# cdf-teensy-interrupter-v2.net
KiCad netlist of a schematic drawn in EAGLE
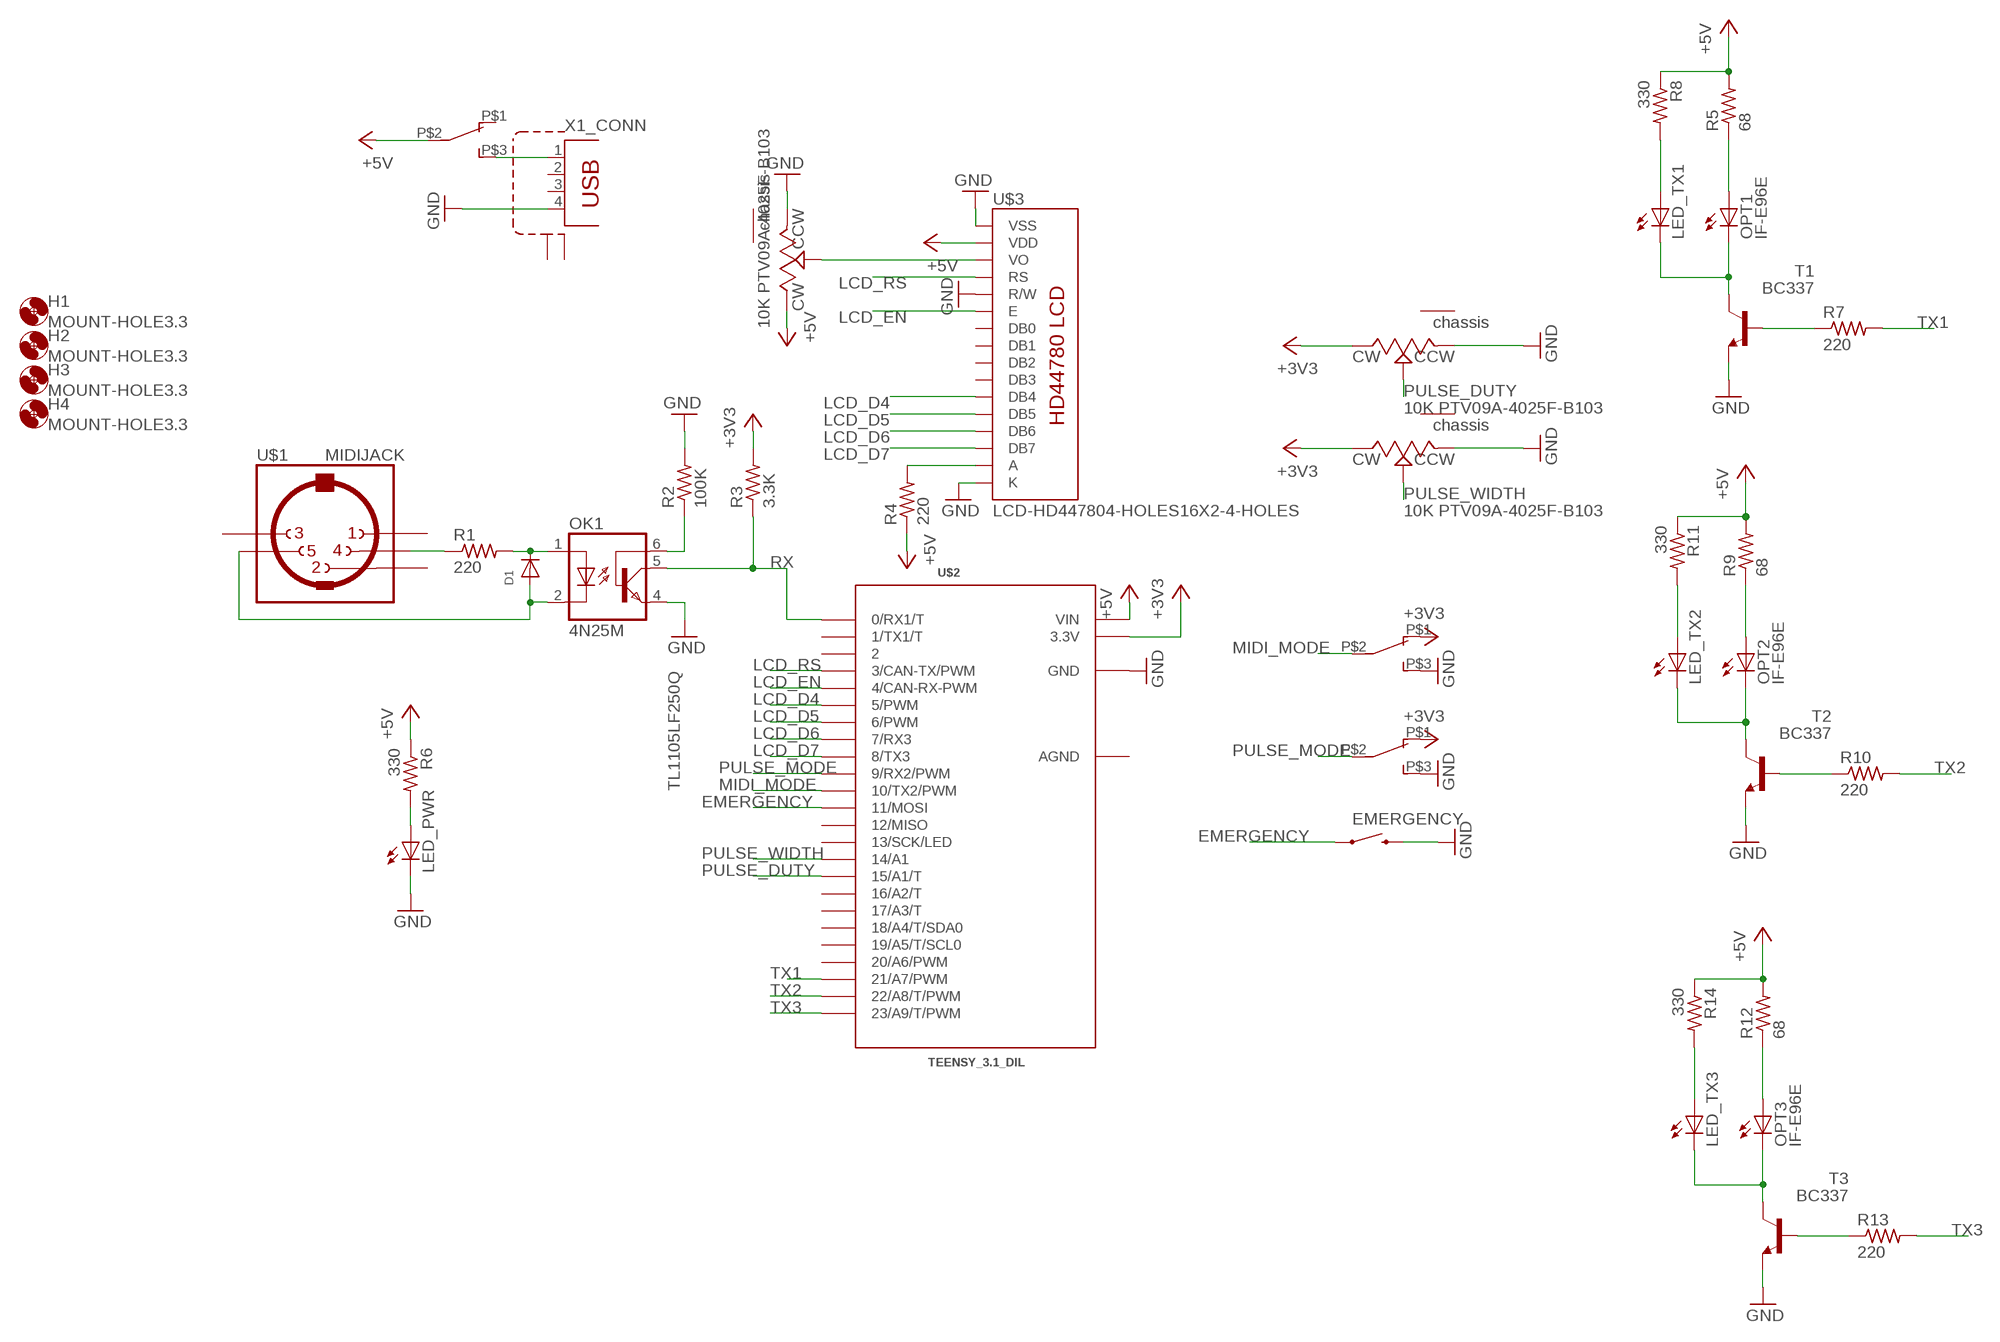
[diagram p0: schematic, sheet 1]

(export (version "E")
  (design (tool "Eeschema 10.0.6"))
  (components
    (comp (ref "D1")
      (value "DIODEDO-1N4148")
      (footprint "eagle-import:DO-1N4148")
      (libsource (lib "eagle-import") (part "DIODEDO-1N4148"))
    )
    (comp (ref "EMERGENCY")
      (value "TL1105LF250Q")
      (footprint "eagle-import:TACTILE-PTH")
      (libsource (lib "eagle-import") (part "SWITCH-MOMENTARY-2PTH"))
    )
    (comp (ref "H1")
      (value "MOUNT-HOLE3.3")
      (footprint "eagle-import:3,3")
      (libsource (lib "eagle-import") (part "MOUNT-HOLE3.3"))
    )
    (comp (ref "H2")
      (value "MOUNT-HOLE3.3")
      (footprint "eagle-import:3,3")
      (libsource (lib "eagle-import") (part "MOUNT-HOLE3.3"))
    )
    (comp (ref "H3")
      (value "MOUNT-HOLE3.3")
      (footprint "eagle-import:3,3")
      (libsource (lib "eagle-import") (part "MOUNT-HOLE3.3"))
    )
    (comp (ref "H4")
      (value "MOUNT-HOLE3.3")
      (footprint "eagle-import:3,3")
      (libsource (lib "eagle-import") (part "MOUNT-HOLE3.3"))
    )
    (comp (ref "LCD_BL")
      (value "10K PTV09A-4025F-B103")
      (footprint "eagle-import:PTV09A-4")
      (libsource (lib "eagle-import") (part "POTENTIOMETERPTV09A_VERTICAL"))
    )
    (comp (ref "LED_PWR")
      (value "LED5MM")
      (footprint "eagle-import:LED5MM")
      (libsource (lib "eagle-import") (part "LED5MM"))
    )
    (comp (ref "LED_TX1")
      (value "LED5MM")
      (footprint "eagle-import:LED5MM")
      (libsource (lib "eagle-import") (part "LED5MM"))
    )
    (comp (ref "LED_TX2")
      (value "LED5MM")
      (footprint "eagle-import:LED5MM")
      (libsource (lib "eagle-import") (part "LED5MM"))
    )
    (comp (ref "LED_TX3")
      (value "LED5MM")
      (footprint "eagle-import:LED5MM")
      (libsource (lib "eagle-import") (part "LED5MM"))
    )
    (comp (ref "MIDI")
      (value "100SP1T1B4M2QE")
      (footprint "eagle-import:100SP1T1B4M2QE")
      (libsource (lib "eagle-import") (part "100SP1T1B4M2QE"))
    )
    (comp (ref "OK1")
      (value "4N25M")
      (footprint "eagle-import:DIL06")
      (fields (field (name "MPN") "4N25-M"))
      (libsource (lib "eagle-import") (part "4N?M25"))
    )
    (comp (ref "OPT1")
      (value "IF-E96E")
      (footprint "eagle-import:IF-E96E")
      (libsource (lib "eagle-import") (part "IF-E96E"))
    )
    (comp (ref "OPT2")
      (value "IF-E96E")
      (footprint "eagle-import:IF-E96E")
      (libsource (lib "eagle-import") (part "IF-E96E"))
    )
    (comp (ref "OPT3")
      (value "IF-E96E")
      (footprint "eagle-import:IF-E96E")
      (libsource (lib "eagle-import") (part "IF-E96E"))
    )
    (comp (ref "PULSE")
      (value "100SP1T1B4M2QE")
      (footprint "eagle-import:100SP1T1B4M2QE")
      (libsource (lib "eagle-import") (part "100SP1T1B4M2QE"))
    )
    (comp (ref "PULSE_DUTY")
      (value "10K PTV09A-4025F-B103")
      (footprint "eagle-import:PTV09A-4")
      (libsource (lib "eagle-import") (part "POTENTIOMETERPTV09A_VERTICAL"))
    )
    (comp (ref "PULSE_WIDTH")
      (value "10K PTV09A-4025F-B103")
      (footprint "eagle-import:PTV09A-4")
      (libsource (lib "eagle-import") (part "POTENTIOMETERPTV09A_VERTICAL"))
    )
    (comp (ref "PWR_SW")
      (value "100SP1T1B4M2QE")
      (footprint "eagle-import:100SP1T1B4M2QE")
      (libsource (lib "eagle-import") (part "100SP1T1B4M2QE"))
    )
    (comp (ref "R1")
      (value "220")
      (footprint "eagle-import:0204_7")
      (libsource (lib "eagle-import") (part "R-US_0204/7"))
    )
    (comp (ref "R2")
      (value "100K")
      (footprint "eagle-import:0204_7")
      (libsource (lib "eagle-import") (part "R-US_0204/7"))
    )
    (comp (ref "R3")
      (value "3.3K")
      (footprint "eagle-import:0204_7")
      (libsource (lib "eagle-import") (part "R-US_0204/7"))
    )
    (comp (ref "R4")
      (value "220")
      (footprint "eagle-import:0204_7")
      (libsource (lib "eagle-import") (part "R-US_0204/7"))
    )
    (comp (ref "R5")
      (value "68")
      (footprint "eagle-import:0204_7")
      (libsource (lib "eagle-import") (part "R-US_0204/7"))
    )
    (comp (ref "R6")
      (value "330")
      (footprint "eagle-import:0204_7")
      (libsource (lib "eagle-import") (part "R-US_0204/7"))
    )
    (comp (ref "R7")
      (value "220")
      (footprint "eagle-import:0204_7")
      (libsource (lib "eagle-import") (part "R-US_0204/7"))
    )
    (comp (ref "R8")
      (value "330")
      (footprint "eagle-import:0204_7")
      (libsource (lib "eagle-import") (part "R-US_0204/7"))
    )
    (comp (ref "R9")
      (value "68")
      (footprint "eagle-import:0204_7")
      (libsource (lib "eagle-import") (part "R-US_0204/7"))
    )
    (comp (ref "R10")
      (value "220")
      (footprint "eagle-import:0204_7")
      (libsource (lib "eagle-import") (part "R-US_0204/7"))
    )
    (comp (ref "R11")
      (value "330")
      (footprint "eagle-import:0204_7")
      (libsource (lib "eagle-import") (part "R-US_0204/7"))
    )
    (comp (ref "R12")
      (value "68")
      (footprint "eagle-import:0204_7")
      (libsource (lib "eagle-import") (part "R-US_0204/7"))
    )
    (comp (ref "R13")
      (value "220")
      (footprint "eagle-import:0204_7")
      (libsource (lib "eagle-import") (part "R-US_0204/7"))
    )
    (comp (ref "R14")
      (value "330")
      (footprint "eagle-import:0204_7")
      (libsource (lib "eagle-import") (part "R-US_0204/7"))
    )
    (comp (ref "T1")
      (value "BC337")
      (footprint "eagle-import:TO92")
      (libsource (lib "eagle-import") (part "BC337"))
    )
    (comp (ref "T2")
      (value "BC337")
      (footprint "eagle-import:TO92")
      (libsource (lib "eagle-import") (part "BC337"))
    )
    (comp (ref "T3")
      (value "BC337")
      (footprint "eagle-import:TO92")
      (libsource (lib "eagle-import") (part "BC337"))
    )
    (comp (ref "U$1")
      (value "MIDIJACK")
      (footprint "eagle-import:CP-2350")
      (libsource (lib "eagle-import") (part "MIDIJACK"))
    )
    (comp (ref "U$2")
      (value "TEENSY_3.1_DIL")
      (footprint "eagle-import:TEENSY3-DIL")
      (libsource (lib "eagle-import") (part "TEENSY_3.1_DIL"))
    )
    (comp (ref "U$3")
      (value "LCD-HD447804-HOLES16X2-4-HOLES")
      (footprint "eagle-import:LCD-16X2-4HOLES")
      (libsource (lib "eagle-import") (part "LCD-HD4478016X2-4-HOLES4-HOLES"))
    )
    (comp (ref "X1")
      (value "TE-292304-1")
      (footprint "eagle-import:TE-292304-1")
      (fields (field (name "MPN") "292304-1 "))
      (libsource (lib "eagle-import") (part "TE-292304-1"))
    )
  )
  (nets
    (net (code "1") (name "+3V3") (class "Default")
      (node (ref "MIDI") (pin "P$1") (pinfunction "1_P$1") (pintype "passive"))
      (node (ref "PULSE") (pin "P$1") (pinfunction "1_P$1") (pintype "passive"))
      (node (ref "PULSE_DUTY") (pin "3") (pinfunction "CW_3") (pintype "passive"))
      (node (ref "PULSE_WIDTH") (pin "3") (pinfunction "CW_3") (pintype "passive"))
      (node (ref "R3") (pin "2") (pinfunction "2_2") (pintype "passive"))
      (node (ref "U$2") (pin "3.3V") (pinfunction "3.3V_3.3V") (pintype "power_in"))
    )
    (net (code "2") (name "+5V") (class "Default")
      (node (ref "LCD_BL") (pin "3") (pinfunction "CW_3") (pintype "passive"))
      (node (ref "PWR_SW") (pin "P$2") (pinfunction "2_P$2") (pintype "passive"))
      (node (ref "R11") (pin "1") (pinfunction "1_1") (pintype "passive"))
      (node (ref "R12") (pin "2") (pinfunction "2_2") (pintype "passive"))
      (node (ref "R14") (pin "1") (pinfunction "1_1") (pintype "passive"))
      (node (ref "R4") (pin "1") (pinfunction "1_1") (pintype "passive"))
      (node (ref "R5") (pin "2") (pinfunction "2_2") (pintype "passive"))
      (node (ref "R6") (pin "1") (pinfunction "1_1") (pintype "passive"))
      (node (ref "R8") (pin "1") (pinfunction "1_1") (pintype "passive"))
      (node (ref "R9") (pin "2") (pinfunction "2_2") (pintype "passive"))
      (node (ref "U$2") (pin "VIN") (pinfunction "VIN_VIN") (pintype "power_in"))
      (node (ref "U$3") (pin "2") (pinfunction "VDD_2") (pintype "power_in"))
    )
    (net (code "3") (name "/AGND") (class "Default")
      (node (ref "U$2") (pin "AGND") (pinfunction "AGND_AGND") (pintype "power_in"))
    )
    (net (code "4") (name "/EMERGENCY") (class "Default")
      (node (ref "EMERGENCY") (pin "1") (pinfunction "1_1") (pintype "passive"))
      (node (ref "U$2") (pin "11") (pinfunction "11/MOSI_11") (pintype "bidirectional"))
    )
    (net (code "5") (name "/LCD_D4") (class "Default")
      (node (ref "U$2") (pin "5") (pinfunction "5/PWM_5") (pintype "bidirectional"))
      (node (ref "U$3") (pin "11") (pinfunction "DB4_11") (pintype "bidirectional"))
    )
    (net (code "6") (name "/LCD_D5") (class "Default")
      (node (ref "U$2") (pin "6") (pinfunction "6/PWM_6") (pintype "bidirectional"))
      (node (ref "U$3") (pin "12") (pinfunction "DB5_12") (pintype "bidirectional"))
    )
    (net (code "7") (name "/LCD_D6") (class "Default")
      (node (ref "U$2") (pin "7") (pinfunction "7/RX3_7") (pintype "bidirectional"))
      (node (ref "U$3") (pin "13") (pinfunction "DB6_13") (pintype "bidirectional"))
    )
    (net (code "8") (name "/LCD_D7") (class "Default")
      (node (ref "U$2") (pin "8") (pinfunction "8/TX3_8") (pintype "bidirectional"))
      (node (ref "U$3") (pin "14") (pinfunction "DB7_14") (pintype "bidirectional"))
    )
    (net (code "9") (name "/LCD_EN") (class "Default")
      (node (ref "U$2") (pin "4") (pinfunction "4/CAN-RX-PWM_4") (pintype "bidirectional"))
      (node (ref "U$3") (pin "6") (pinfunction "E_6") (pintype "input"))
    )
    (net (code "10") (name "/LCD_RS") (class "Default")
      (node (ref "U$2") (pin "3") (pinfunction "3/CAN-TX/PWM_3") (pintype "bidirectional"))
      (node (ref "U$3") (pin "4") (pinfunction "RS_4") (pintype "input"))
    )
    (net (code "11") (name "/MIDI_MODE") (class "Default")
      (node (ref "MIDI") (pin "P$2") (pinfunction "2_P$2") (pintype "passive"))
      (node (ref "U$2") (pin "10") (pinfunction "10/TX2/PWM_10") (pintype "bidirectional"))
    )
    (net (code "12") (name "/PULSE_DUTY") (class "Default")
      (node (ref "PULSE_DUTY") (pin "2") (pinfunction "WIPER_2") (pintype "passive"))
      (node (ref "U$2") (pin "15/A1") (pinfunction "15/A1/T_15/A1") (pintype "bidirectional"))
    )
    (net (code "13") (name "/PULSE_MODE") (class "Default")
      (node (ref "PULSE") (pin "P$2") (pinfunction "2_P$2") (pintype "passive"))
      (node (ref "U$2") (pin "9") (pinfunction "9/RX2/PWM_9") (pintype "bidirectional"))
    )
    (net (code "14") (name "/PULSE_WIDTH") (class "Default")
      (node (ref "PULSE_WIDTH") (pin "2") (pinfunction "WIPER_2") (pintype "passive"))
      (node (ref "U$2") (pin "14/A0") (pinfunction "14/A1_14/A0") (pintype "bidirectional"))
    )
    (net (code "15") (name "/RX") (class "Default")
      (node (ref "OK1") (pin "5") (pinfunction "COL_5") (pintype "passive"))
      (node (ref "R3") (pin "1") (pinfunction "1_1") (pintype "passive"))
      (node (ref "U$2") (pin "0") (pinfunction "0/RX1/T_0") (pintype "bidirectional"))
    )
    (net (code "16") (name "/TX1") (class "Default")
      (node (ref "R7") (pin "2") (pinfunction "2_2") (pintype "passive"))
      (node (ref "U$2") (pin "21/A7") (pinfunction "21/A7/PWM_21/A7") (pintype "bidirectional"))
    )
    (net (code "17") (name "/TX2") (class "Default")
      (node (ref "R10") (pin "2") (pinfunction "2_2") (pintype "passive"))
      (node (ref "U$2") (pin "22/A8") (pinfunction "22/A8/T/PWM_22/A8") (pintype "bidirectional"))
    )
    (net (code "18") (name "/TX3") (class "Default")
      (node (ref "R13") (pin "2") (pinfunction "2_2") (pintype "passive"))
      (node (ref "U$2") (pin "23/A9") (pinfunction "23/A9/T/PWM_23/A9") (pintype "bidirectional"))
    )
    (net (code "19") (name "GND") (class "Default")
      (node (ref "EMERGENCY") (pin "3") (pinfunction "2_3") (pintype "passive"))
      (node (ref "LCD_BL") (pin "1") (pinfunction "CCW_1") (pintype "passive"))
      (node (ref "LED_PWR") (pin "K") (pinfunction "C_K") (pintype "passive"))
      (node (ref "MIDI") (pin "P$3") (pinfunction "3_P$3") (pintype "passive"))
      (node (ref "OK1") (pin "4") (pinfunction "EMI_4") (pintype "passive"))
      (node (ref "PULSE") (pin "P$3") (pinfunction "3_P$3") (pintype "passive"))
      (node (ref "PULSE_DUTY") (pin "1") (pinfunction "CCW_1") (pintype "passive"))
      (node (ref "PULSE_WIDTH") (pin "1") (pinfunction "CCW_1") (pintype "passive"))
      (node (ref "R2") (pin "2") (pinfunction "2_2") (pintype "passive"))
      (node (ref "T1") (pin "1") (pinfunction "E_1") (pintype "passive"))
      (node (ref "T2") (pin "1") (pinfunction "E_1") (pintype "passive"))
      (node (ref "T3") (pin "1") (pinfunction "E_1") (pintype "passive"))
      (node (ref "U$2") (pin "GND") (pinfunction "GND_GND") (pintype "power_in"))
      (node (ref "U$3") (pin "1") (pinfunction "VSS_1") (pintype "power_in"))
      (node (ref "U$3") (pin "16") (pinfunction "K_16") (pintype "power_in"))
      (node (ref "U$3") (pin "5") (pinfunction "R/W_5") (pintype "input"))
      (node (ref "X1") (pin "4") (pinfunction "4_4") (pintype "bidirectional"))
    )
    (net (code "20") (name "Net-(LCD_BL-WIPER)") (class "Default")
      (node (ref "LCD_BL") (pin "2") (pinfunction "WIPER_2") (pintype "passive"))
      (node (ref "U$3") (pin "3") (pinfunction "VO_3") (pintype "bidirectional"))
    )
    (net (code "21") (name "Net-(LED_PWR-PadA)") (class "Default")
      (node (ref "LED_PWR") (pin "A") (pinfunction "A_A") (pintype "passive"))
      (node (ref "R6") (pin "2") (pinfunction "2_2") (pintype "passive"))
    )
    (net (code "22") (name "Net-(LED_TX1-C)") (class "Default")
      (node (ref "LED_TX1") (pin "K") (pinfunction "C_K") (pintype "passive"))
      (node (ref "OPT1") (pin "P$1_CATHODE-") (pinfunction "C_P$1_CATHODE-") (pintype "passive"))
      (node (ref "T1") (pin "3") (pinfunction "C_3") (pintype "passive"))
    )
    (net (code "23") (name "Net-(LED_TX1-PadA)") (class "Default")
      (node (ref "LED_TX1") (pin "A") (pinfunction "A_A") (pintype "passive"))
      (node (ref "R8") (pin "2") (pinfunction "2_2") (pintype "passive"))
    )
    (net (code "24") (name "Net-(LED_TX2-C)") (class "Default")
      (node (ref "LED_TX2") (pin "K") (pinfunction "C_K") (pintype "passive"))
      (node (ref "OPT2") (pin "P$1_CATHODE-") (pinfunction "C_P$1_CATHODE-") (pintype "passive"))
      (node (ref "T2") (pin "3") (pinfunction "C_3") (pintype "passive"))
    )
    (net (code "25") (name "Net-(LED_TX2-PadA)") (class "Default")
      (node (ref "LED_TX2") (pin "A") (pinfunction "A_A") (pintype "passive"))
      (node (ref "R11") (pin "2") (pinfunction "2_2") (pintype "passive"))
    )
    (net (code "26") (name "Net-(LED_TX3-C)") (class "Default")
      (node (ref "LED_TX3") (pin "K") (pinfunction "C_K") (pintype "passive"))
      (node (ref "OPT3") (pin "P$1_CATHODE-") (pinfunction "C_P$1_CATHODE-") (pintype "passive"))
      (node (ref "T3") (pin "3") (pinfunction "C_3") (pintype "passive"))
    )
    (net (code "27") (name "Net-(LED_TX3-PadA)") (class "Default")
      (node (ref "LED_TX3") (pin "A") (pinfunction "A_A") (pintype "passive"))
      (node (ref "R14") (pin "2") (pinfunction "2_2") (pintype "passive"))
    )
    (net (code "28") (name "Net-(OK1-A)") (class "Default")
      (node (ref "D1") (pin "C") (pinfunction "C_C") (pintype "passive"))
      (node (ref "OK1") (pin "1") (pinfunction "A_1") (pintype "passive"))
      (node (ref "R1") (pin "2") (pinfunction "2_2") (pintype "passive"))
    )
    (net (code "29") (name "Net-(OK1-BAS)") (class "Default")
      (node (ref "OK1") (pin "6") (pinfunction "BAS_6") (pintype "passive"))
      (node (ref "R2") (pin "1") (pinfunction "1_1") (pintype "passive"))
    )
    (net (code "30") (name "Net-(OK1-C)") (class "Default")
      (node (ref "D1") (pin "A") (pinfunction "A_A") (pintype "passive"))
      (node (ref "OK1") (pin "2") (pinfunction "C_2") (pintype "passive"))
      (node (ref "U$1") (pin "5") (pinfunction "5_5") (pintype "passive"))
    )
    (net (code "31") (name "Net-(OPT1-A)") (class "Default")
      (node (ref "OPT1") (pin "P$2_ANODE+") (pinfunction "A_P$2_ANODE+") (pintype "passive"))
      (node (ref "R5") (pin "1") (pinfunction "1_1") (pintype "passive"))
    )
    (net (code "32") (name "Net-(OPT2-A)") (class "Default")
      (node (ref "OPT2") (pin "P$2_ANODE+") (pinfunction "A_P$2_ANODE+") (pintype "passive"))
      (node (ref "R9") (pin "1") (pinfunction "1_1") (pintype "passive"))
    )
    (net (code "33") (name "Net-(OPT3-A)") (class "Default")
      (node (ref "OPT3") (pin "P$2_ANODE+") (pinfunction "A_P$2_ANODE+") (pintype "passive"))
      (node (ref "R12") (pin "1") (pinfunction "1_1") (pintype "passive"))
    )
    (net (code "34") (name "Net-(PWR_SW-3)") (class "Default")
      (node (ref "PWR_SW") (pin "P$3") (pinfunction "3_P$3") (pintype "passive"))
      (node (ref "X1") (pin "1") (pinfunction "1_1") (pintype "bidirectional"))
    )
    (net (code "35") (name "Net-(R1-Pad1)") (class "Default")
      (node (ref "R1") (pin "1") (pinfunction "1_1") (pintype "passive"))
      (node (ref "U$1") (pin "4") (pinfunction "4_4") (pintype "passive"))
    )
    (net (code "36") (name "Net-(T1-B)") (class "Default")
      (node (ref "R7") (pin "1") (pinfunction "1_1") (pintype "passive"))
      (node (ref "T1") (pin "2") (pinfunction "B_2") (pintype "passive"))
    )
    (net (code "37") (name "Net-(T2-B)") (class "Default")
      (node (ref "R10") (pin "1") (pinfunction "1_1") (pintype "passive"))
      (node (ref "T2") (pin "2") (pinfunction "B_2") (pintype "passive"))
    )
    (net (code "38") (name "Net-(T3-B)") (class "Default")
      (node (ref "R13") (pin "1") (pinfunction "1_1") (pintype "passive"))
      (node (ref "T3") (pin "2") (pinfunction "B_2") (pintype "passive"))
    )
    (net (code "39") (name "Net-(U$3-A)") (class "Default")
      (node (ref "R4") (pin "2") (pinfunction "2_2") (pintype "passive"))
      (node (ref "U$3") (pin "15") (pinfunction "A_15") (pintype "power_in"))
    )
    (net (code "40") (name "unconnected-(LCD_BL-CHASSIS-Pad4)") (class "Default")
      (node (ref "LCD_BL") (pin "4") (pinfunction "CHASSIS_4") (pintype "passive"))
    )
    (net (code "41") (name "unconnected-(PULSE_DUTY-CHASSIS-Pad4)") (class "Default")
      (node (ref "PULSE_DUTY") (pin "4") (pinfunction "CHASSIS_4") (pintype "passive"))
    )
    (net (code "42") (name "unconnected-(PULSE_WIDTH-CHASSIS-Pad4)") (class "Default")
      (node (ref "PULSE_WIDTH") (pin "4") (pinfunction "CHASSIS_4") (pintype "passive"))
    )
    (net (code "43") (name "unconnected-(PWR_SW-1-PadP$1)") (class "Default")
      (node (ref "PWR_SW") (pin "P$1") (pinfunction "1_P$1") (pintype "passive"))
    )
    (net (code "44") (name "unconnected-(U$1-Pad1)") (class "Default")
      (node (ref "U$1") (pin "1") (pinfunction "1_1") (pintype "passive"))
    )
    (net (code "45") (name "unconnected-(U$1-Pad2)") (class "Default")
      (node (ref "U$1") (pin "2") (pinfunction "2_2") (pintype "passive"))
    )
    (net (code "46") (name "unconnected-(U$1-Pad3)") (class "Default")
      (node (ref "U$1") (pin "3") (pinfunction "3_3") (pintype "passive"))
    )
    (net (code "47") (name "unconnected-(U$2-1{slash}TX1{slash}T-Pad1)") (class "Default")
      (node (ref "U$2") (pin "1") (pinfunction "1/TX1/T_1") (pintype "bidirectional"))
    )
    (net (code "48") (name "unconnected-(U$2-12{slash}MISO-Pad12)") (class "Default")
      (node (ref "U$2") (pin "12") (pinfunction "12/MISO_12") (pintype "bidirectional"))
    )
    (net (code "49") (name "unconnected-(U$2-13{slash}SCK{slash}LED-Pad13)") (class "Default")
      (node (ref "U$2") (pin "13") (pinfunction "13/SCK/LED_13") (pintype "bidirectional"))
    )
    (net (code "50") (name "unconnected-(U$2-16{slash}A2{slash}T-Pad16{slash}A2)") (class "Default")
      (node (ref "U$2") (pin "16/A2") (pinfunction "16/A2/T_16/A2") (pintype "bidirectional"))
    )
    (net (code "51") (name "unconnected-(U$2-17{slash}A3{slash}T-Pad17{slash}A3)") (class "Default")
      (node (ref "U$2") (pin "17/A3") (pinfunction "17/A3/T_17/A3") (pintype "bidirectional"))
    )
    (net (code "52") (name "unconnected-(U$2-18{slash}A4{slash}T{slash}SDA0-Pad18{slash}A4)") (class "Default")
      (node (ref "U$2") (pin "18/A4") (pinfunction "18/A4/T/SDA0_18/A4") (pintype "bidirectional"))
    )
    (net (code "53") (name "unconnected-(U$2-19{slash}A5{slash}T{slash}SCL0-Pad19{slash}A5)") (class "Default")
      (node (ref "U$2") (pin "19/A5") (pinfunction "19/A5/T/SCL0_19/A5") (pintype "bidirectional"))
    )
    (net (code "54") (name "unconnected-(U$2-20{slash}A6{slash}PWM-Pad20{slash}A6)") (class "Default")
      (node (ref "U$2") (pin "20/A6") (pinfunction "20/A6/PWM_20/A6") (pintype "bidirectional"))
    )
    (net (code "55") (name "unconnected-(U$2-Pad2)") (class "Default")
      (node (ref "U$2") (pin "2") (pinfunction "2_2") (pintype "bidirectional"))
    )
    (net (code "56") (name "unconnected-(U$3-DB0-Pad7)") (class "Default")
      (node (ref "U$3") (pin "7") (pinfunction "DB0_7") (pintype "bidirectional"))
    )
    (net (code "57") (name "unconnected-(U$3-DB1-Pad8)") (class "Default")
      (node (ref "U$3") (pin "8") (pinfunction "DB1_8") (pintype "bidirectional"))
    )
    (net (code "58") (name "unconnected-(U$3-DB2-Pad9)") (class "Default")
      (node (ref "U$3") (pin "9") (pinfunction "DB2_9") (pintype "bidirectional"))
    )
    (net (code "59") (name "unconnected-(U$3-DB3-Pad10)") (class "Default")
      (node (ref "U$3") (pin "10") (pinfunction "DB3_10") (pintype "bidirectional"))
    )
    (net (code "60") (name "unconnected-(X1-Pad2)") (class "Default")
      (node (ref "X1") (pin "2") (pinfunction "2_2") (pintype "bidirectional"))
    )
    (net (code "61") (name "unconnected-(X1-Pad3)") (class "Default")
      (node (ref "X1") (pin "3") (pinfunction "3_3") (pintype "bidirectional"))
    )
    (net (code "62") (name "unconnected-(X1A-S1-PadP$1)") (class "Default")
      (node (ref "X1") (pin "P$1") (pinfunction "S1_P$1") (pintype "passive"))
    )
    (net (code "63") (name "unconnected-(X1A-S2-PadP$2)") (class "Default")
      (node (ref "X1") (pin "P$2") (pinfunction "S2_P$2") (pintype "passive"))
    )
  )
)
